# combined-board_external-wires.net
KiCad netlist of a schematic drawn in EAGLE
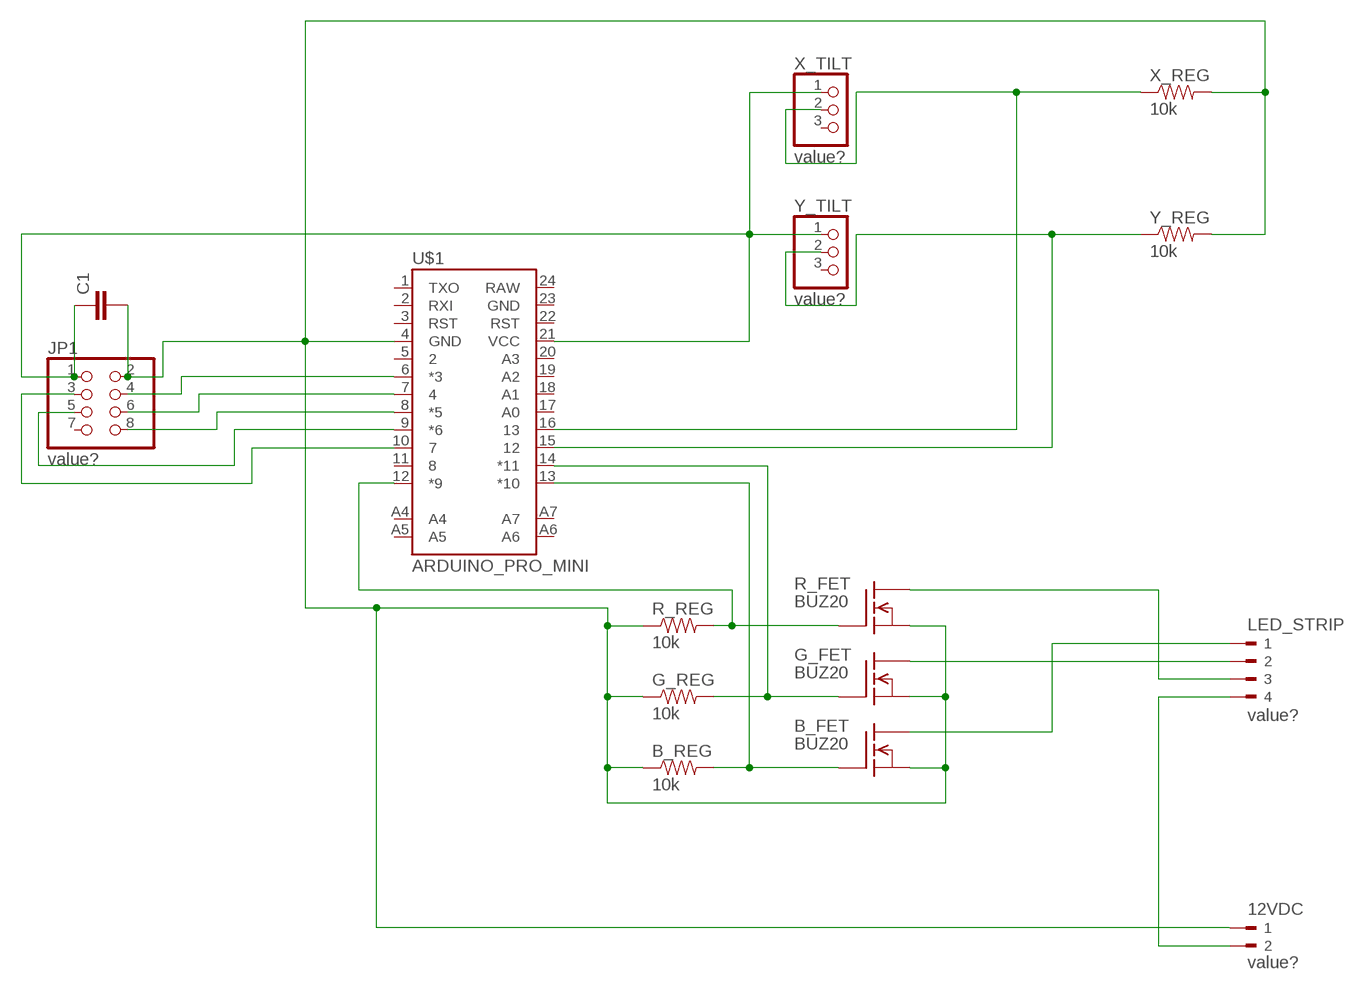
[diagram p0: schematic, sheet 1]

(export (version "E")
  (design (tool "Eeschema 10.0.6"))
  (components
    (comp (ref "12VDC")
      (value "value?")
      (footprint "eagle-import:180-2")
      (libsource (lib "eagle-import") (part "180-2"))
    )
    (comp (ref "B_FET")
      (value "BUZ20")
      (footprint "eagle-import:TO220")
      (libsource (lib "eagle-import") (part "BUZ20"))
    )
    (comp (ref "B_REG")
      (value "10k")
      (footprint "eagle-import:AXIAL-0.4")
      (libsource (lib "eagle-import") (part "RESISTORPTH-1/4W"))
    )
    (comp (ref "C1")
      (value "CAPPTH")
      (footprint "eagle-import:CAP-PTH-SMALL")
      (libsource (lib "eagle-import") (part "CAPPTH"))
    )
    (comp (ref "G_FET")
      (value "BUZ20")
      (footprint "eagle-import:TO220")
      (libsource (lib "eagle-import") (part "BUZ20"))
    )
    (comp (ref "G_REG")
      (value "10k")
      (footprint "eagle-import:AXIAL-0.4")
      (libsource (lib "eagle-import") (part "RESISTORPTH-1/4W"))
    )
    (comp (ref "JP1")
      (value "value?")
      (footprint "eagle-import:2X04")
      (libsource (lib "eagle-import") (part "PINHD-2X4"))
    )
    (comp (ref "LED_STRIP")
      (value "value?")
      (footprint "eagle-import:180-4")
      (libsource (lib "eagle-import") (part "180-4"))
    )
    (comp (ref "R_FET")
      (value "BUZ20")
      (footprint "eagle-import:TO220")
      (libsource (lib "eagle-import") (part "BUZ20"))
    )
    (comp (ref "R_REG")
      (value "10k")
      (footprint "eagle-import:AXIAL-0.4")
      (libsource (lib "eagle-import") (part "RESISTORPTH-1/4W"))
    )
    (comp (ref "U$1")
      (value "ARDUINO_PRO_MINI")
      (footprint "eagle-import:ARDUINO_PRO_MINI")
      (libsource (lib "eagle-import") (part "ARDUINO_PRO_MINI"))
    )
    (comp (ref "X_REG")
      (value "10k")
      (footprint "eagle-import:AXIAL-0.4")
      (libsource (lib "eagle-import") (part "RESISTORPTH-1/4W"))
    )
    (comp (ref "X_TILT")
      (value "value?")
      (footprint "eagle-import:1X03")
      (libsource (lib "eagle-import") (part "PINHD-1X3"))
    )
    (comp (ref "Y_REG")
      (value "10k")
      (footprint "eagle-import:AXIAL-0.4")
      (libsource (lib "eagle-import") (part "RESISTORPTH-1/4W"))
    )
    (comp (ref "Y_TILT")
      (value "value?")
      (footprint "eagle-import:1X03")
      (libsource (lib "eagle-import") (part "PINHD-1X3"))
    )
  )
  (nets
    (net (code "1") (name "Net-(12VDC-Pad2)") (class "Default")
      (node (ref "12VDC") (pin "2") (pinfunction "2_2") (pintype "passive"))
      (node (ref "LED_STRIP") (pin "4") (pinfunction "4_4") (pintype "passive"))
    )
    (net (code "2") (name "Net-(B_FET-D)") (class "Default")
      (node (ref "B_FET") (pin "2") (pinfunction "D_2") (pintype "passive"))
      (node (ref "LED_STRIP") (pin "1") (pinfunction "1_1") (pintype "passive"))
    )
    (net (code "3") (name "Net-(B_FET-G)") (class "Default")
      (node (ref "B_FET") (pin "1") (pinfunction "G_1") (pintype "passive"))
      (node (ref "B_REG") (pin "P$2") (pinfunction "2_P$2") (pintype "passive"))
      (node (ref "U$1") (pin "13") (pinfunction "*10_13") (pintype "bidirectional"))
    )
    (net (code "4") (name "Net-(B_FET-S)") (class "Default")
      (node (ref "12VDC") (pin "1") (pinfunction "1_1") (pintype "passive"))
      (node (ref "B_FET") (pin "3") (pinfunction "S_3") (pintype "passive"))
      (node (ref "B_REG") (pin "P$1") (pinfunction "1_P$1") (pintype "passive"))
      (node (ref "C1") (pin "2") (pinfunction "2_2") (pintype "passive"))
      (node (ref "G_FET") (pin "3") (pinfunction "S_3") (pintype "passive"))
      (node (ref "G_REG") (pin "P$1") (pinfunction "1_P$1") (pintype "passive"))
      (node (ref "JP1") (pin "2") (pinfunction "2_2") (pintype "passive"))
      (node (ref "R_FET") (pin "3") (pinfunction "S_3") (pintype "passive"))
      (node (ref "R_REG") (pin "P$1") (pinfunction "1_P$1") (pintype "passive"))
      (node (ref "U$1") (pin "4") (pinfunction "GND_4") (pintype "bidirectional"))
      (node (ref "X_REG") (pin "P$2") (pinfunction "2_P$2") (pintype "passive"))
      (node (ref "Y_REG") (pin "P$2") (pinfunction "2_P$2") (pintype "passive"))
    )
    (net (code "5") (name "Net-(G_FET-D)") (class "Default")
      (node (ref "G_FET") (pin "2") (pinfunction "D_2") (pintype "passive"))
      (node (ref "LED_STRIP") (pin "2") (pinfunction "2_2") (pintype "passive"))
    )
    (net (code "6") (name "Net-(G_FET-G)") (class "Default")
      (node (ref "G_FET") (pin "1") (pinfunction "G_1") (pintype "passive"))
      (node (ref "G_REG") (pin "P$2") (pinfunction "2_P$2") (pintype "passive"))
      (node (ref "U$1") (pin "14") (pinfunction "*11_14") (pintype "bidirectional"))
    )
    (net (code "7") (name "Net-(R_FET-D)") (class "Default")
      (node (ref "LED_STRIP") (pin "3") (pinfunction "3_3") (pintype "passive"))
      (node (ref "R_FET") (pin "2") (pinfunction "D_2") (pintype "passive"))
    )
    (net (code "8") (name "Net-(R_FET-G)") (class "Default")
      (node (ref "R_FET") (pin "1") (pinfunction "G_1") (pintype "passive"))
      (node (ref "R_REG") (pin "P$2") (pinfunction "2_P$2") (pintype "passive"))
      (node (ref "U$1") (pin "12") (pinfunction "*9_12") (pintype "bidirectional"))
    )
    (net (code "9") (name "Net-(U$1-*3)") (class "Default")
      (node (ref "JP1") (pin "4") (pinfunction "4_4") (pintype "passive"))
      (node (ref "U$1") (pin "6") (pinfunction "*3_6") (pintype "bidirectional"))
    )
    (net (code "10") (name "Net-(U$1-*5)") (class "Default")
      (node (ref "JP1") (pin "8") (pinfunction "8_8") (pintype "passive"))
      (node (ref "U$1") (pin "8") (pinfunction "*5_8") (pintype "bidirectional"))
    )
    (net (code "11") (name "Net-(U$1-*6)") (class "Default")
      (node (ref "JP1") (pin "5") (pinfunction "5_5") (pintype "passive"))
      (node (ref "U$1") (pin "9") (pinfunction "*6_9") (pintype "bidirectional"))
    )
    (net (code "12") (name "Net-(U$1-4)") (class "Default")
      (node (ref "JP1") (pin "6") (pinfunction "6_6") (pintype "passive"))
      (node (ref "U$1") (pin "7") (pinfunction "4_7") (pintype "bidirectional"))
    )
    (net (code "13") (name "Net-(U$1-7)") (class "Default")
      (node (ref "JP1") (pin "3") (pinfunction "3_3") (pintype "passive"))
      (node (ref "U$1") (pin "10") (pinfunction "7_10") (pintype "bidirectional"))
    )
    (net (code "14") (name "Net-(U$1-12)") (class "Default")
      (node (ref "U$1") (pin "15") (pinfunction "12_15") (pintype "bidirectional"))
      (node (ref "Y_REG") (pin "P$1") (pinfunction "1_P$1") (pintype "passive"))
      (node (ref "Y_TILT") (pin "2") (pinfunction "2_2") (pintype "passive"))
    )
    (net (code "15") (name "Net-(U$1-13)") (class "Default")
      (node (ref "U$1") (pin "16") (pinfunction "13_16") (pintype "bidirectional"))
      (node (ref "X_REG") (pin "P$1") (pinfunction "1_P$1") (pintype "passive"))
      (node (ref "X_TILT") (pin "2") (pinfunction "2_2") (pintype "passive"))
    )
    (net (code "16") (name "Net-(U$1-VCC)") (class "Default")
      (node (ref "C1") (pin "1") (pinfunction "1_1") (pintype "passive"))
      (node (ref "JP1") (pin "1") (pinfunction "1_1") (pintype "passive"))
      (node (ref "U$1") (pin "21") (pinfunction "VCC_21") (pintype "bidirectional"))
      (node (ref "X_TILT") (pin "1") (pinfunction "1_1") (pintype "passive"))
      (node (ref "Y_TILT") (pin "1") (pinfunction "1_1") (pintype "passive"))
    )
    (net (code "17") (name "unconnected-(JP1-Pad7)") (class "Default")
      (node (ref "JP1") (pin "7") (pinfunction "7_7") (pintype "passive"))
    )
    (net (code "18") (name "unconnected-(U$1-2-Pad5)") (class "Default")
      (node (ref "U$1") (pin "5") (pinfunction "2_5") (pintype "bidirectional"))
    )
    (net (code "19") (name "unconnected-(U$1-8-Pad11)") (class "Default")
      (node (ref "U$1") (pin "11") (pinfunction "8_11") (pintype "bidirectional"))
    )
    (net (code "20") (name "unconnected-(U$1-A0-Pad17)") (class "Default")
      (node (ref "U$1") (pin "17") (pinfunction "A0_17") (pintype "bidirectional"))
    )
    (net (code "21") (name "unconnected-(U$1-A1-Pad18)") (class "Default")
      (node (ref "U$1") (pin "18") (pinfunction "A1_18") (pintype "bidirectional"))
    )
    (net (code "22") (name "unconnected-(U$1-A2-Pad19)") (class "Default")
      (node (ref "U$1") (pin "19") (pinfunction "A2_19") (pintype "bidirectional"))
    )
    (net (code "23") (name "unconnected-(U$1-A3-Pad20)") (class "Default")
      (node (ref "U$1") (pin "20") (pinfunction "A3_20") (pintype "bidirectional"))
    )
    (net (code "24") (name "unconnected-(U$1-GND-Pad23)") (class "Default")
      (node (ref "U$1") (pin "23") (pinfunction "GND_23") (pintype "bidirectional"))
    )
    (net (code "25") (name "unconnected-(U$1-PadA4)") (class "Default")
      (node (ref "U$1") (pin "A4") (pinfunction "A4_A4") (pintype "bidirectional"))
    )
    (net (code "26") (name "unconnected-(U$1-PadA5)") (class "Default")
      (node (ref "U$1") (pin "A5") (pinfunction "A5_A5") (pintype "bidirectional"))
    )
    (net (code "27") (name "unconnected-(U$1-PadA6)") (class "Default")
      (node (ref "U$1") (pin "A6") (pinfunction "A6_A6") (pintype "bidirectional"))
    )
    (net (code "28") (name "unconnected-(U$1-PadA7)") (class "Default")
      (node (ref "U$1") (pin "A7") (pinfunction "A7_A7") (pintype "bidirectional"))
    )
    (net (code "29") (name "unconnected-(U$1-RAW-Pad24)") (class "Default")
      (node (ref "U$1") (pin "24") (pinfunction "RAW_24") (pintype "bidirectional"))
    )
    (net (code "30") (name "unconnected-(U$1-RST-Pad3)") (class "Default")
      (node (ref "U$1") (pin "3") (pinfunction "RST_3") (pintype "bidirectional"))
    )
    (net (code "31") (name "unconnected-(U$1-RST-Pad22)") (class "Default")
      (node (ref "U$1") (pin "22") (pinfunction "RST_22") (pintype "bidirectional"))
    )
    (net (code "32") (name "unconnected-(U$1-RXI-Pad2)") (class "Default")
      (node (ref "U$1") (pin "2") (pinfunction "RXI_2") (pintype "bidirectional"))
    )
    (net (code "33") (name "unconnected-(U$1-TXO-Pad1)") (class "Default")
      (node (ref "U$1") (pin "1") (pinfunction "TXO_1") (pintype "bidirectional"))
    )
    (net (code "34") (name "unconnected-(X_TILT-Pad3)") (class "Default")
      (node (ref "X_TILT") (pin "3") (pinfunction "3_3") (pintype "passive"))
    )
    (net (code "35") (name "unconnected-(Y_TILT-Pad3)") (class "Default")
      (node (ref "Y_TILT") (pin "3") (pinfunction "3_3") (pintype "passive"))
    )
  )
)
